# 12_to__5.net
KiCad netlist of a schematic drawn in Altium Designer
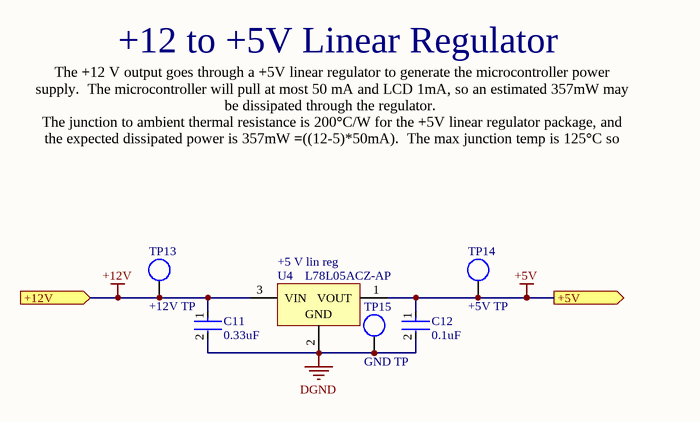
[diagram p0: +12_to_+5.SchDoc]

(export (version "E")
  (design (tool "Eeschema 10.0.6"))
  (components
    (comp (ref "C11")
      (value "0.33uF")
      (footprint "FP-C0805C-DG-MFG")
      (description "CAP CER 10UF 10V X5R 0805")
      (fields (field (name "TOLERANCE") "10%") (field (name "MANUFACTURER PART NUMBER") "C0805C106K8PACTU"))
      (libsource (lib "Altium Content Vault") (part "11868f565c42a9108669ba33697ecf6"))
    )
    (comp (ref "C12")
      (value "0.1uF")
      (footprint "FP-C0805C-DG-MFG")
      (description "CAP CER 10UF 10V X5R 0805")
      (fields (field (name "TOLERANCE") "10%") (field (name "MANUFACTURER PART NUMBER") "C0805C106K8PACTU"))
      (libsource (lib "Altium Content Vault") (part "11868f565c42a9108669ba33697ecf6"))
    )
    (comp (ref "TP13")
      (value "+12V TP")
      (footprint "PCBComponent_1")
      (libsource (lib "test-point") (part "Component_1"))
    )
    (comp (ref "TP14")
      (value "+5V TP")
      (footprint "PCBComponent_1")
      (libsource (lib "test-point") (part "Component_1"))
    )
    (comp (ref "TP15")
      (value "GND TP")
      (footprint "PCBComponent_1")
      (libsource (lib "test-point") (part "Component_1"))
    )
    (comp (ref "U4")
      (value "L78L05ACZ-AP")
      (footprint "TO-92")
      (description "Positive Voltage Regulator, 5V, 3-Pin TO-92")
      (libsource (lib "Altium Content Vault") (part "PM-REG-7805-SIL3"))
    )
  )
  (nets
    (net (code "1") (name "+5V") (class "Default")
      (node (ref "C12") (pin "1") (pinfunction "1_1") (pintype "passive"))
      (node (ref "TP14") (pin "TP") (pinfunction "TP_TP") (pintype "passive"))
      (node (ref "U4") (pin "1") (pinfunction "VOUT_1") (pintype "power_in"))
    )
    (net (code "2") (name "+12V") (class "Default")
      (node (ref "C11") (pin "1") (pinfunction "1_1") (pintype "passive"))
      (node (ref "TP13") (pin "TP") (pinfunction "TP_TP") (pintype "passive"))
      (node (ref "U4") (pin "3") (pinfunction "VIN_3") (pintype "power_in"))
    )
    (net (code "3") (name "DGND") (class "Default")
      (node (ref "C11") (pin "2") (pinfunction "2_2") (pintype "passive"))
      (node (ref "C12") (pin "2") (pinfunction "2_2") (pintype "passive"))
      (node (ref "TP15") (pin "TP") (pinfunction "TP_TP") (pintype "passive"))
      (node (ref "U4") (pin "2") (pinfunction "GND_2") (pintype "power_in"))
    )
  )
)
